# ADC_1W.net
KiCad netlist of a schematic drawn in Altium Designer
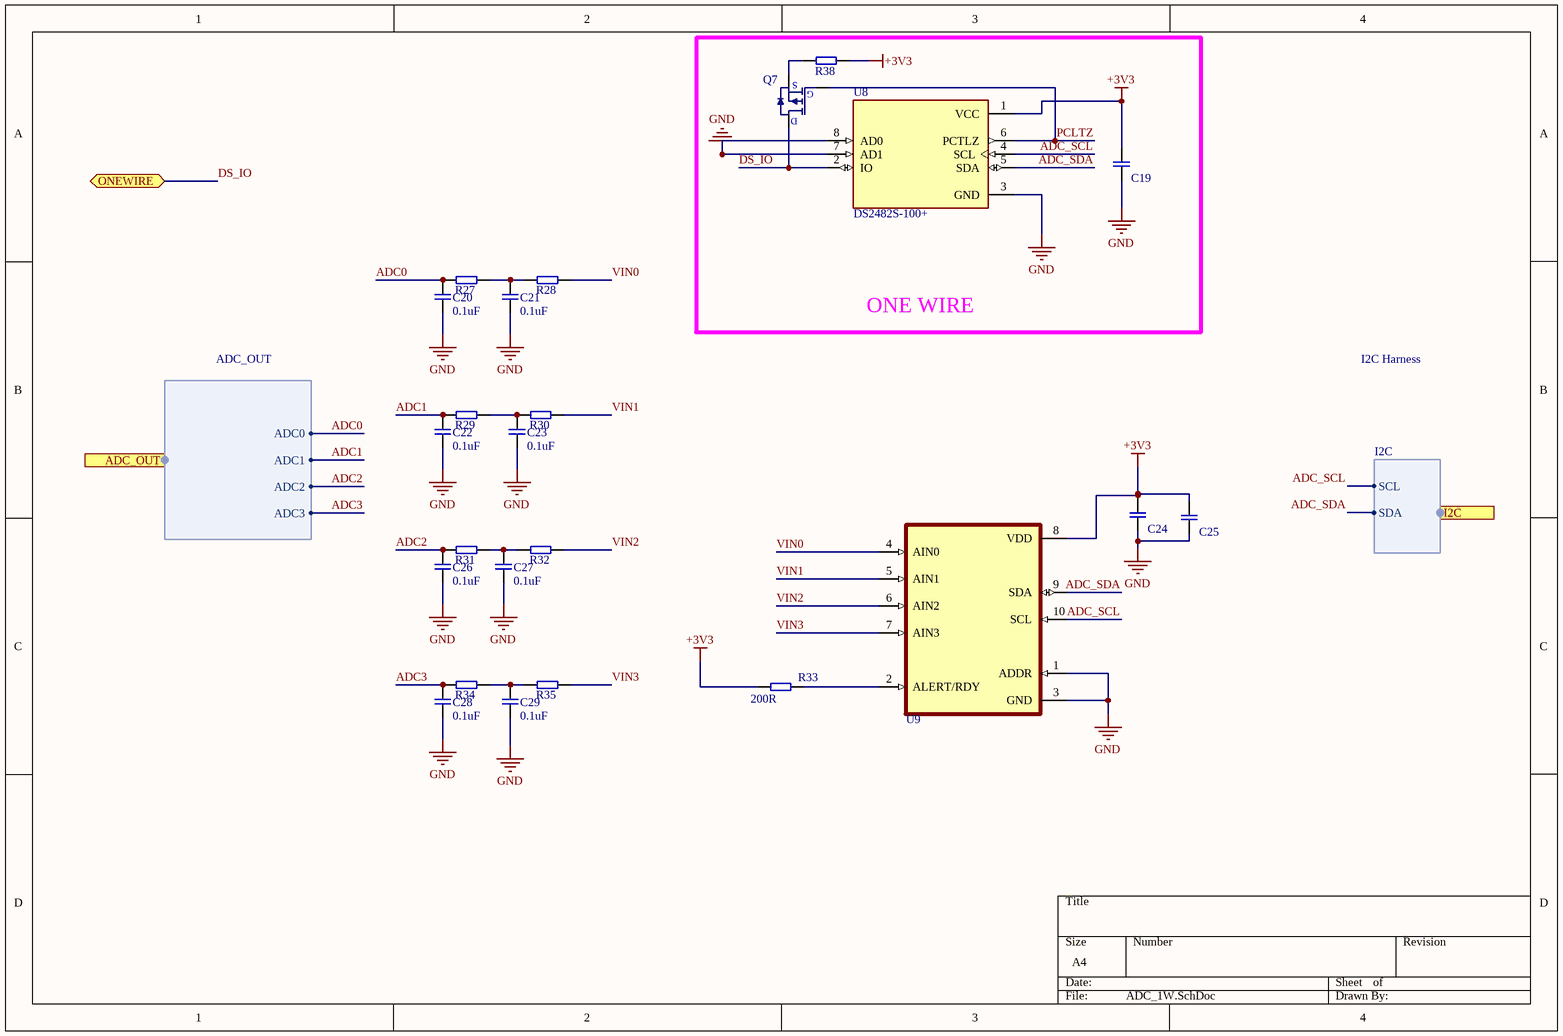
[diagram p0: ADC_1W.SchDoc]

(export (version "E")
  (design (tool "Eeschema 10.0.6"))
  (components
    (comp (ref "C19")
      (value "1uF")
      (footprint "C0603")
      (description "CAP CER 1UF 16V X5R 0603")
      (fields (field (name "PART NUMBER") "GMC10X5R105K16NT") (field (name "VOLTAGE") "16V"))
      (libsource (lib "anayurt") (part "CAP"))
    )
    (comp (ref "C20")
      (value "0.1uF")
      (footprint "C0402")
      (description "CAP CER 0.1UF 10V X5R 0402")
      (fields (field (name "PART NUMBER") "C1005X5R1A104K050BA") (field (name "VOLTAGE") "10V"))
      (libsource (lib "anayurt") (part "CAP"))
    )
    (comp (ref "C21")
      (value "0.1uF")
      (footprint "C0402")
      (description "CAP CER 0.1UF 10V X5R 0402")
      (fields (field (name "PART NUMBER") "C1005X5R1A104K050BA") (field (name "VOLTAGE") "10V"))
      (libsource (lib "anayurt") (part "CAP"))
    )
    (comp (ref "C22")
      (value "0.1uF")
      (footprint "C0402")
      (description "CAP CER 0.1UF 10V X5R 0402")
      (fields (field (name "PART NUMBER") "C1005X5R1A104K050BA") (field (name "VOLTAGE") "10V"))
      (libsource (lib "anayurt") (part "CAP"))
    )
    (comp (ref "C23")
      (value "0.1uF")
      (footprint "C0402")
      (description "CAP CER 0.1UF 10V X5R 0402")
      (fields (field (name "PART NUMBER") "C1005X5R1A104K050BA") (field (name "VOLTAGE") "10V"))
      (libsource (lib "anayurt") (part "CAP"))
    )
    (comp (ref "C24")
      (value "1uF")
      (footprint "C0603")
      (description "CAP CER 1UF 16V X5R 0603")
      (fields (field (name "PART NUMBER") "GMC10X5R105K16NT") (field (name "VOLTAGE") "16V"))
      (libsource (lib "anayurt") (part "CAP"))
    )
    (comp (ref "C25")
      (value "10uF")
      (footprint "C0603")
      (description "CAP CER 10UF 16V X5R 0603")
      (fields (field (name "PART NUMBER") "GRT188R61C106KE13D") (field (name "VOLTAGE") "16V"))
      (libsource (lib "anayurt") (part "CAP"))
    )
    (comp (ref "C26")
      (value "0.1uF")
      (footprint "C0402")
      (description "CAP CER 0.1UF 10V X5R 0402")
      (fields (field (name "PART NUMBER") "C1005X5R1A104K050BA") (field (name "VOLTAGE") "10V"))
      (libsource (lib "anayurt") (part "CAP"))
    )
    (comp (ref "C27")
      (value "0.1uF")
      (footprint "C0402")
      (description "CAP CER 0.1UF 10V X5R 0402")
      (fields (field (name "PART NUMBER") "C1005X5R1A104K050BA") (field (name "VOLTAGE") "10V"))
      (libsource (lib "anayurt") (part "CAP"))
    )
    (comp (ref "C28")
      (value "0.1uF")
      (footprint "C0402")
      (description "CAP CER 0.1UF 10V X5R 0402")
      (fields (field (name "PART NUMBER") "C1005X5R1A104K050BA") (field (name "VOLTAGE") "10V"))
      (libsource (lib "anayurt") (part "CAP"))
    )
    (comp (ref "C29")
      (value "0.1uF")
      (footprint "C0402")
      (description "CAP CER 0.1UF 10V X5R 0402")
      (fields (field (name "PART NUMBER") "C1005X5R1A104K050BA") (field (name "VOLTAGE") "10V"))
      (libsource (lib "anayurt") (part "CAP"))
    )
    (comp (ref "Q7")
      (value "AO3415A")
      (footprint "SOT-23")
      (description "MOSFET P-CH 20V 5A SOT23-3L")
      (fields
        (field (name "VOLTAGE") "1.5V,4.5V")
        (field (name "MANUFACTURER") "Alpha & Omega Semiconductor Inc.")
      )
      (libsource (lib "anayurt") (part "PMOS"))
    )
    (comp (ref "R27")
      (value "200R")
      (footprint "R0402")
      (description "RES.(1005) 0402 200 Ohms 1% 1/16W 100PPM")
      (fields (field (name "PART NUMBER") "0402WGF2000TCE"))
      (libsource (lib "anayurt") (part "RES"))
    )
    (comp (ref "R28")
      (value "200R")
      (footprint "R0402")
      (description "RES.(1005) 0402 200 Ohms 1% 1/16W 100PPM")
      (fields (field (name "PART NUMBER") "0402WGF2000TCE"))
      (libsource (lib "anayurt") (part "RES"))
    )
    (comp (ref "R29")
      (value "200R")
      (footprint "R0402")
      (description "RES.(1005) 0402 200 Ohms 1% 1/16W 100PPM")
      (fields (field (name "PART NUMBER") "0402WGF2000TCE"))
      (libsource (lib "anayurt") (part "RES"))
    )
    (comp (ref "R30")
      (value "200R")
      (footprint "R0402")
      (description "RES.(1005) 0402 200 Ohms 1% 1/16W 100PPM")
      (fields (field (name "PART NUMBER") "0402WGF2000TCE"))
      (libsource (lib "anayurt") (part "RES"))
    )
    (comp (ref "R31")
      (value "200R")
      (footprint "R0402")
      (description "RES.(1005) 0402 200 Ohms 1% 1/16W 100PPM")
      (fields (field (name "PART NUMBER") "0402WGF2000TCE"))
      (libsource (lib "anayurt") (part "RES"))
    )
    (comp (ref "R32")
      (value "200R")
      (footprint "R0402")
      (description "RES.(1005) 0402 200 Ohms 1% 1/16W 100PPM")
      (fields (field (name "PART NUMBER") "0402WGF2000TCE"))
      (libsource (lib "anayurt") (part "RES"))
    )
    (comp (ref "R33")
      (value "200R")
      (footprint "R0402")
      (description "RES.(1005) 0402 200 Ohms 1% 1/16W 100PPM")
      (fields (field (name "PART NUMBER") "0402WGF2000TCE"))
      (libsource (lib "anayurt") (part "RES"))
    )
    (comp (ref "R34")
      (value "200R")
      (footprint "R0402")
      (description "RES.(1005) 0402 200 Ohms 1% 1/16W 100PPM")
      (fields (field (name "PART NUMBER") "0402WGF2000TCE"))
      (libsource (lib "anayurt") (part "RES"))
    )
    (comp (ref "R35")
      (value "200R")
      (footprint "R0402")
      (description "RES.(1005) 0402 200 Ohms 1% 1/16W 100PPM")
      (fields (field (name "PART NUMBER") "0402WGF2000TCE"))
      (libsource (lib "anayurt") (part "RES"))
    )
    (comp (ref "R38")
      (value "1K")
      (footprint "R0402")
      (description "RES SMD 1K OHM 0.1% 1/16W 0402")
      (fields (field (name "PART NUMBER") "RT0402BRE071KL") (field (name "TOLERANCE") "0.1%"))
      (libsource (lib "anayurt") (part "RES"))
    )
    (comp (ref "U8")
      (value "DS2482S-100+")
      (footprint "SOIC127P600X175-8N")
      (description "IC BRIDGE I2C TO 1-WIRE 8-SOIC")
      (fields (field (name "MF") "Maxim Integrated"))
      (libsource (lib "anayurt") (part "DS2482S-100+"))
    )
    (comp (ref "U9")
      (value "ADS1115IDGST")
      (footprint "ADS1115IDGST")
      (description "IC ADC 16BIT SIGMA-DELTA 10VSSOP")
      (fields (field (name "MANUFACTURER") "Texas Instruments"))
      (libsource (lib "anayurt") (part "ADS1115IDGST"))
    )
  )
  (nets
    (net (code "3") (name "+3V3") (class "Default")
      (node (ref "C19") (pin "2") (pinfunction "2_2") (pintype "passive"))
      (node (ref "C24") (pin "2") (pinfunction "2_2") (pintype "passive"))
      (node (ref "C25") (pin "2") (pinfunction "2_2") (pintype "passive"))
      (node (ref "R33") (pin "1") (pinfunction "1_1") (pintype "passive"))
      (node (ref "R38") (pin "1") (pinfunction "1_1") (pintype "passive"))
      (node (ref "U8") (pin "1") (pinfunction "VCC_1") (pintype "power_in"))
      (node (ref "U9") (pin "8") (pinfunction "VDD_8") (pintype "power_in"))
    )
    (net (code "4") (name "/ADC0") (class "Default")
      (node (ref "C20") (pin "2") (pinfunction "2_2") (pintype "passive"))
      (node (ref "R27") (pin "2") (pinfunction "2_2") (pintype "passive"))
    )
    (net (code "5") (name "/ADC1") (class "Default")
      (node (ref "C22") (pin "2") (pinfunction "2_2") (pintype "passive"))
      (node (ref "R29") (pin "2") (pinfunction "2_2") (pintype "passive"))
    )
    (net (code "6") (name "/ADC2") (class "Default")
      (node (ref "C26") (pin "2") (pinfunction "2_2") (pintype "passive"))
      (node (ref "R31") (pin "2") (pinfunction "2_2") (pintype "passive"))
    )
    (net (code "7") (name "/ADC3") (class "Default")
      (node (ref "C28") (pin "2") (pinfunction "2_2") (pintype "passive"))
      (node (ref "R34") (pin "2") (pinfunction "2_2") (pintype "passive"))
    )
    (net (code "8") (name "/ADC_SCL") (class "Default")
      (node (ref "U8") (pin "4") (pinfunction "SCL_4") (pintype "input"))
      (node (ref "U9") (pin "10") (pinfunction "SCL_10") (pintype "input"))
    )
    (net (code "9") (name "/ADC_SDA") (class "Default")
      (node (ref "U8") (pin "5") (pinfunction "SDA_5") (pintype "bidirectional"))
      (node (ref "U9") (pin "9") (pinfunction "SDA_9") (pintype "bidirectional"))
    )
    (net (code "10") (name "/DS_IO") (class "Default")
      (node (ref "Q7") (pin "3") (pinfunction "D_3") (pintype "passive"))
      (node (ref "U8") (pin "2") (pinfunction "IO_2") (pintype "bidirectional"))
    )
    (net (code "11") (name "/PCLTZ") (class "Default")
      (node (ref "Q7") (pin "1") (pinfunction "G_1") (pintype "passive"))
      (node (ref "U8") (pin "6") (pinfunction "PCTLZ_6") (pintype "output"))
    )
    (net (code "12") (name "/VIN0") (class "Default")
      (node (ref "R28") (pin "1") (pinfunction "1_1") (pintype "passive"))
      (node (ref "U9") (pin "4") (pinfunction "AIN0_4") (pintype "input"))
    )
    (net (code "13") (name "/VIN1") (class "Default")
      (node (ref "R30") (pin "1") (pinfunction "1_1") (pintype "passive"))
      (node (ref "U9") (pin "5") (pinfunction "AIN1_5") (pintype "input"))
    )
    (net (code "14") (name "/VIN2") (class "Default")
      (node (ref "R32") (pin "1") (pinfunction "1_1") (pintype "passive"))
      (node (ref "U9") (pin "6") (pinfunction "AIN2_6") (pintype "input"))
    )
    (net (code "15") (name "/VIN3") (class "Default")
      (node (ref "R35") (pin "1") (pinfunction "1_1") (pintype "passive"))
      (node (ref "U9") (pin "7") (pinfunction "AIN3_7") (pintype "input"))
    )
    (net (code "18") (name "GND") (class "Default")
      (node (ref "C19") (pin "1") (pinfunction "1_1") (pintype "passive"))
      (node (ref "C20") (pin "1") (pinfunction "1_1") (pintype "passive"))
      (node (ref "C21") (pin "1") (pinfunction "1_1") (pintype "passive"))
      (node (ref "C22") (pin "1") (pinfunction "1_1") (pintype "passive"))
      (node (ref "C23") (pin "1") (pinfunction "1_1") (pintype "passive"))
      (node (ref "C24") (pin "1") (pinfunction "1_1") (pintype "passive"))
      (node (ref "C25") (pin "1") (pinfunction "1_1") (pintype "passive"))
      (node (ref "C26") (pin "1") (pinfunction "1_1") (pintype "passive"))
      (node (ref "C27") (pin "1") (pinfunction "1_1") (pintype "passive"))
      (node (ref "C28") (pin "1") (pinfunction "1_1") (pintype "passive"))
      (node (ref "C29") (pin "1") (pinfunction "1_1") (pintype "passive"))
      (node (ref "U8") (pin "3") (pinfunction "GND_3") (pintype "power_in"))
      (node (ref "U8") (pin "7") (pinfunction "AD1_7") (pintype "input"))
      (node (ref "U8") (pin "8") (pinfunction "AD0_8") (pintype "input"))
      (node (ref "U9") (pin "1") (pinfunction "ADDR_1") (pintype "input"))
      (node (ref "U9") (pin "3") (pinfunction "GND_3") (pintype "power_in"))
    )
    (net (code "19") (name "Net-(C21-Pad2)") (class "Default")
      (node (ref "C21") (pin "2") (pinfunction "2_2") (pintype "passive"))
      (node (ref "R27") (pin "1") (pinfunction "1_1") (pintype "passive"))
      (node (ref "R28") (pin "2") (pinfunction "2_2") (pintype "passive"))
    )
    (net (code "20") (name "Net-(C23-Pad2)") (class "Default")
      (node (ref "C23") (pin "2") (pinfunction "2_2") (pintype "passive"))
      (node (ref "R29") (pin "1") (pinfunction "1_1") (pintype "passive"))
      (node (ref "R30") (pin "2") (pinfunction "2_2") (pintype "passive"))
    )
    (net (code "21") (name "Net-(C27-Pad2)") (class "Default")
      (node (ref "C27") (pin "2") (pinfunction "2_2") (pintype "passive"))
      (node (ref "R31") (pin "1") (pinfunction "1_1") (pintype "passive"))
      (node (ref "R32") (pin "2") (pinfunction "2_2") (pintype "passive"))
    )
    (net (code "22") (name "Net-(C29-Pad2)") (class "Default")
      (node (ref "C29") (pin "2") (pinfunction "2_2") (pintype "passive"))
      (node (ref "R34") (pin "1") (pinfunction "1_1") (pintype "passive"))
      (node (ref "R35") (pin "2") (pinfunction "2_2") (pintype "passive"))
    )
    (net (code "23") (name "Net-(Q7-S)") (class "Default")
      (node (ref "Q7") (pin "2") (pinfunction "S_2") (pintype "passive"))
      (node (ref "R38") (pin "2") (pinfunction "2_2") (pintype "passive"))
    )
    (net (code "24") (name "Net-(U9-ALERT{slash}RDY)") (class "Default")
      (node (ref "R33") (pin "2") (pinfunction "2_2") (pintype "passive"))
      (node (ref "U9") (pin "2") (pinfunction "ALERT/RDY_2") (pintype "input"))
    )
  )
)
